# clock.net
KiCad netlist of a schematic drawn in EAGLE
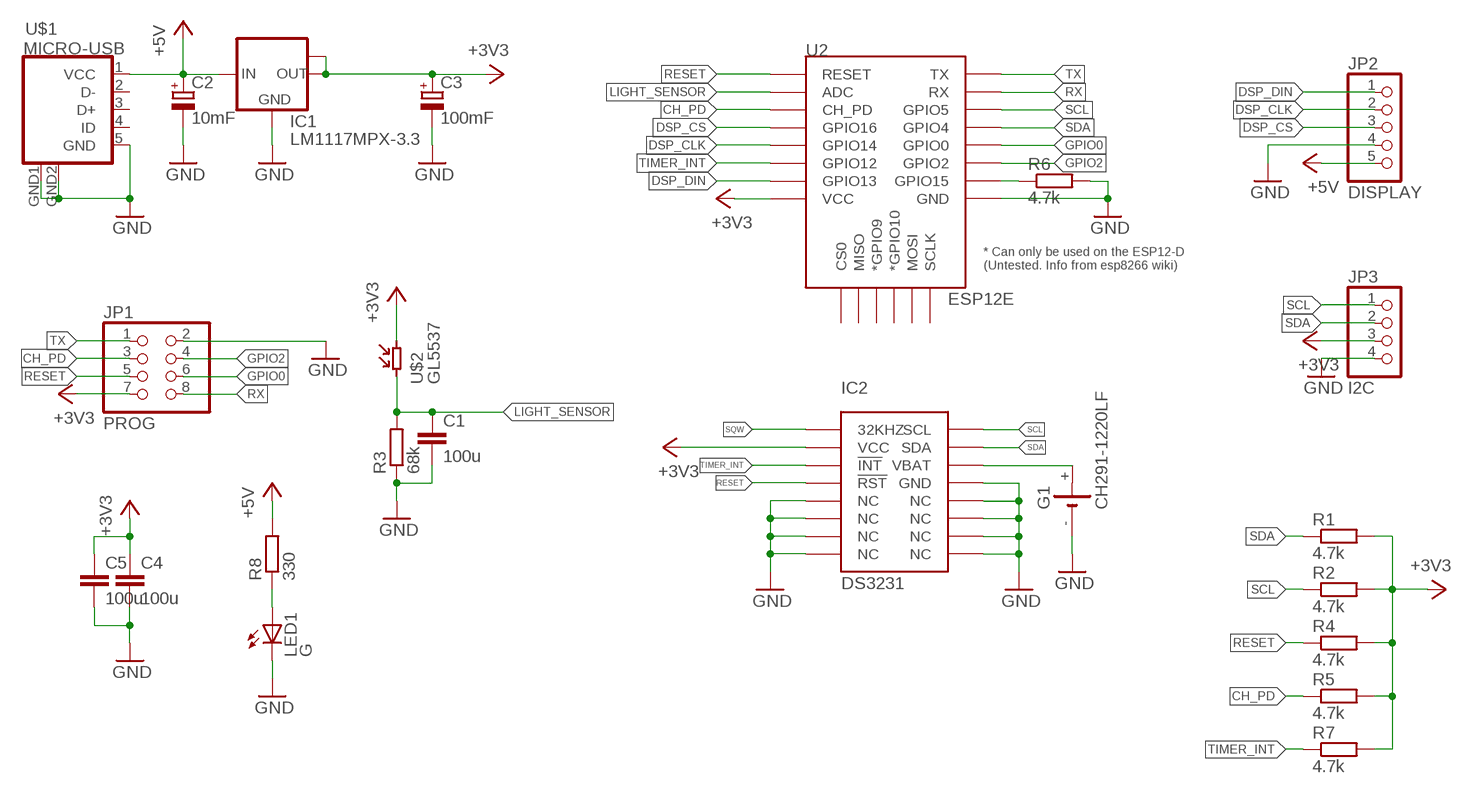
[diagram p0: schematic, sheet 1]

(export (version "E")
  (design (tool "Eeschema 10.0.6"))
  (components
    (comp (ref "C1")
      (value "100u")
      (footprint "eagle-import:C0805")
      (libsource (lib "eagle-import") (part "C-EUC0805"))
    )
    (comp (ref "C2")
      (value "10mF")
      (footprint "eagle-import:A_3216-18W")
      (libsource (lib "eagle-import") (part "CPOL-EUA/3216-18W"))
    )
    (comp (ref "C3")
      (value "100mF")
      (footprint "eagle-import:A_3216-18W")
      (libsource (lib "eagle-import") (part "CPOL-EUA/3216-18W"))
    )
    (comp (ref "C4")
      (value "100u")
      (footprint "eagle-import:C0805")
      (libsource (lib "eagle-import") (part "C-EUC0805"))
    )
    (comp (ref "C5")
      (value "100u")
      (footprint "eagle-import:C0805")
      (libsource (lib "eagle-import") (part "C-EUC0805"))
    )
    (comp (ref "G1")
      (value "CH291-1220LF")
      (footprint "eagle-import:CH291-1220LF")
      (libsource (lib "eagle-import") (part "CH291-1220LF"))
    )
    (comp (ref "IC1")
      (value "LM1117MPX-3.3")
      (footprint "eagle-import:SOT223")
      (libsource (lib "eagle-import") (part "LM1117MPX-3.3"))
    )
    (comp (ref "IC2")
      (value "DS3231")
      (footprint "eagle-import:SOIC-16W")
      (libsource (lib "eagle-import") (part "DS3231SOIC-16W"))
    )
    (comp (ref "JP1")
      (value "PROG")
      (footprint "eagle-import:2X04")
      (libsource (lib "eagle-import") (part "PINHD-2X4"))
    )
    (comp (ref "JP2")
      (value "DISPLAY")
      (footprint "eagle-import:1X05")
      (libsource (lib "eagle-import") (part "PINHD-1X5"))
    )
    (comp (ref "JP3")
      (value "I2C")
      (footprint "eagle-import:1X04")
      (libsource (lib "eagle-import") (part "PINHD-1X4"))
    )
    (comp (ref "LED1")
      (value "G")
      (footprint "eagle-import:CHIPLED_0805")
      (libsource (lib "eagle-import") (part "LEDCHIPLED_0805"))
    )
    (comp (ref "R1")
      (value "4.7k")
      (footprint "eagle-import:M0805")
      (libsource (lib "eagle-import") (part "R-EU_M0805"))
    )
    (comp (ref "R2")
      (value "4.7k")
      (footprint "eagle-import:M0805")
      (libsource (lib "eagle-import") (part "R-EU_M0805"))
    )
    (comp (ref "R3")
      (value "68k")
      (footprint "eagle-import:M0805")
      (libsource (lib "eagle-import") (part "R-EU_M0805"))
    )
    (comp (ref "R4")
      (value "4.7k")
      (footprint "eagle-import:M0805")
      (libsource (lib "eagle-import") (part "R-EU_M0805"))
    )
    (comp (ref "R5")
      (value "4.7k")
      (footprint "eagle-import:M0805")
      (libsource (lib "eagle-import") (part "R-EU_M0805"))
    )
    (comp (ref "R6")
      (value "4.7k")
      (footprint "eagle-import:M0805")
      (libsource (lib "eagle-import") (part "R-EU_M0805"))
    )
    (comp (ref "R7")
      (value "4.7k")
      (footprint "eagle-import:M0805")
      (libsource (lib "eagle-import") (part "R-EU_M0805"))
    )
    (comp (ref "R8")
      (value "330")
      (footprint "eagle-import:M0805")
      (libsource (lib "eagle-import") (part "R-EU_M0805"))
    )
    (comp (ref "U$1")
      (value "MICRO-USB")
      (footprint "eagle-import:MICRO-USB")
      (libsource (lib "eagle-import") (part "MICRO-USB"))
    )
    (comp (ref "U$2")
      (value "GL5537")
      (footprint "eagle-import:GL55")
      (libsource (lib "eagle-import") (part "GL5537"))
    )
    (comp (ref "U2")
      (value "ESP12E")
      (footprint "eagle-import:ESP12E-SMD")
      (libsource (lib "eagle-import") (part "ESP12ESMD"))
    )
  )
  (nets
    (net (code "1") (name "+3V3") (class "Default")
      (node (ref "C3") (pin "+") (pinfunction "+_+") (pintype "passive"))
      (node (ref "C4") (pin "1") (pinfunction "1_1") (pintype "passive"))
      (node (ref "C5") (pin "1") (pinfunction "1_1") (pintype "passive"))
      (node (ref "IC1") (pin "2") (pinfunction "OUT_2") (pintype "passive"))
      (node (ref "IC1") (pin "TAB") (pinfunction "OUT1_TAB") (pintype "passive"))
      (node (ref "IC2") (pin "2") (pinfunction "VCC_2") (pintype "bidirectional"))
      (node (ref "JP1") (pin "7") (pinfunction "7_7") (pintype "passive"))
      (node (ref "JP3") (pin "3") (pinfunction "3_3") (pintype "passive"))
      (node (ref "R1") (pin "2") (pinfunction "2_2") (pintype "passive"))
      (node (ref "R2") (pin "2") (pinfunction "2_2") (pintype "passive"))
      (node (ref "R4") (pin "2") (pinfunction "2_2") (pintype "passive"))
      (node (ref "R5") (pin "2") (pinfunction "2_2") (pintype "passive"))
      (node (ref "R7") (pin "2") (pinfunction "2_2") (pintype "passive"))
      (node (ref "U$2") (pin "P$2") (pinfunction "P$2_P$2") (pintype "passive"))
      (node (ref "U2") (pin "VCC") (pinfunction "VCC_VCC") (pintype "bidirectional"))
    )
    (net (code "2") (name "+5V") (class "Default")
      (node (ref "C2") (pin "+") (pinfunction "+_+") (pintype "passive"))
      (node (ref "IC1") (pin "3") (pinfunction "IN_3") (pintype "input"))
      (node (ref "JP2") (pin "5") (pinfunction "5_5") (pintype "passive"))
      (node (ref "R8") (pin "2") (pinfunction "2_2") (pintype "passive"))
      (node (ref "U$1") (pin "1") (pinfunction "VCC_1") (pintype "power_in"))
    )
    (net (code "3") (name "CH_PD") (class "Default")
      (node (ref "JP1") (pin "3") (pinfunction "3_3") (pintype "passive"))
      (node (ref "R5") (pin "1") (pinfunction "1_1") (pintype "passive"))
      (node (ref "U2") (pin "CH_PD") (pinfunction "CH_PD_CH_PD") (pintype "bidirectional"))
    )
    (net (code "4") (name "DSP_CLK") (class "Default")
      (node (ref "JP2") (pin "2") (pinfunction "2_2") (pintype "passive"))
      (node (ref "U2") (pin "GPIO14") (pinfunction "GPIO14_GPIO14") (pintype "bidirectional"))
    )
    (net (code "5") (name "DSP_CS") (class "Default")
      (node (ref "JP2") (pin "3") (pinfunction "3_3") (pintype "passive"))
      (node (ref "U2") (pin "GPIO16") (pinfunction "GPIO16_GPIO16") (pintype "bidirectional"))
    )
    (net (code "6") (name "DSP_DIN") (class "Default")
      (node (ref "JP2") (pin "1") (pinfunction "1_1") (pintype "passive"))
      (node (ref "U2") (pin "GPIO13") (pinfunction "GPIO13_GPIO13") (pintype "bidirectional"))
    )
    (net (code "7") (name "GND") (class "Default")
      (node (ref "C1") (pin "2") (pinfunction "2_2") (pintype "passive"))
      (node (ref "C2") (pin "-") (pinfunction "-_-") (pintype "passive"))
      (node (ref "C3") (pin "-") (pinfunction "-_-") (pintype "passive"))
      (node (ref "C4") (pin "2") (pinfunction "2_2") (pintype "passive"))
      (node (ref "C5") (pin "2") (pinfunction "2_2") (pintype "passive"))
      (node (ref "G1") (pin "-") (pinfunction "-_-") (pintype "passive"))
      (node (ref "IC1") (pin "1") (pinfunction "GND_1") (pintype "input"))
      (node (ref "IC2") (pin "10") (pinfunction "NC_10") (pintype "bidirectional"))
      (node (ref "IC2") (pin "11") (pinfunction "NC_11") (pintype "bidirectional"))
      (node (ref "IC2") (pin "12") (pinfunction "NC_12") (pintype "bidirectional"))
      (node (ref "IC2") (pin "13") (pinfunction "GND_13") (pintype "bidirectional"))
      (node (ref "IC2") (pin "5") (pinfunction "NC_5") (pintype "bidirectional"))
      (node (ref "IC2") (pin "6") (pinfunction "NC_6") (pintype "bidirectional"))
      (node (ref "IC2") (pin "7") (pinfunction "NC_7") (pintype "bidirectional"))
      (node (ref "IC2") (pin "8") (pinfunction "NC_8") (pintype "bidirectional"))
      (node (ref "IC2") (pin "9") (pinfunction "NC_9") (pintype "bidirectional"))
      (node (ref "JP1") (pin "2") (pinfunction "2_2") (pintype "passive"))
      (node (ref "JP2") (pin "4") (pinfunction "4_4") (pintype "passive"))
      (node (ref "JP3") (pin "4") (pinfunction "4_4") (pintype "passive"))
      (node (ref "LED1") (pin "C") (pinfunction "C_C") (pintype "passive"))
      (node (ref "R3") (pin "1") (pinfunction "1_1") (pintype "passive"))
      (node (ref "R6") (pin "2") (pinfunction "2_2") (pintype "passive"))
      (node (ref "U$1") (pin "5") (pinfunction "GND_5") (pintype "power_in"))
      (node (ref "U$1") (pin "GND1") (pinfunction "GND_GND1") (pintype "power_in"))
      (node (ref "U$1") (pin "GND2") (pinfunction "GND_GND2") (pintype "power_in"))
      (node (ref "U2") (pin "GND") (pinfunction "GND_GND") (pintype "bidirectional"))
    )
    (net (code "8") (name "GPIO0") (class "Default")
      (node (ref "JP1") (pin "6") (pinfunction "6_6") (pintype "passive"))
      (node (ref "U2") (pin "GPIO0") (pinfunction "GPIO0_GPIO0") (pintype "bidirectional"))
    )
    (net (code "9") (name "GPIO2") (class "Default")
      (node (ref "JP1") (pin "4") (pinfunction "4_4") (pintype "passive"))
      (node (ref "U2") (pin "GPIO2") (pinfunction "GPIO2_GPIO2") (pintype "bidirectional"))
    )
    (net (code "10") (name "LIGHT_SENSOR") (class "Default")
      (node (ref "C1") (pin "1") (pinfunction "1_1") (pintype "passive"))
      (node (ref "R3") (pin "2") (pinfunction "2_2") (pintype "passive"))
      (node (ref "U$2") (pin "P$1") (pinfunction "P$1_P$1") (pintype "passive"))
      (node (ref "U2") (pin "ADC") (pinfunction "ADC_ADC") (pintype "bidirectional"))
    )
    (net (code "11") (name "Net-(IC2-VBAT)") (class "Default")
      (node (ref "G1") (pin "+") (pinfunction "+_+") (pintype "passive"))
      (node (ref "IC2") (pin "14") (pinfunction "VBAT_14") (pintype "bidirectional"))
    )
    (net (code "12") (name "Net-(LED1-PadA)") (class "Default")
      (node (ref "LED1") (pin "A") (pinfunction "A_A") (pintype "passive"))
      (node (ref "R8") (pin "1") (pinfunction "1_1") (pintype "passive"))
    )
    (net (code "13") (name "Net-(R6-Pad1)") (class "Default")
      (node (ref "R6") (pin "1") (pinfunction "1_1") (pintype "passive"))
      (node (ref "U2") (pin "GPIO15") (pinfunction "GPIO15_GPIO15") (pintype "bidirectional"))
    )
    (net (code "14") (name "RESET") (class "Default")
      (node (ref "IC2") (pin "4") (pinfunction "~{RST}_4") (pintype "bidirectional"))
      (node (ref "JP1") (pin "5") (pinfunction "5_5") (pintype "passive"))
      (node (ref "R4") (pin "1") (pinfunction "1_1") (pintype "passive"))
      (node (ref "U2") (pin "RESET") (pinfunction "RESET_RESET") (pintype "bidirectional"))
    )
    (net (code "15") (name "RX") (class "Default")
      (node (ref "JP1") (pin "8") (pinfunction "8_8") (pintype "passive"))
      (node (ref "U2") (pin "RXD0") (pinfunction "RX_RXD0") (pintype "bidirectional"))
    )
    (net (code "16") (name "SCL") (class "Default")
      (node (ref "IC2") (pin "16") (pinfunction "SCL_16") (pintype "bidirectional"))
      (node (ref "JP3") (pin "1") (pinfunction "1_1") (pintype "passive"))
      (node (ref "R2") (pin "1") (pinfunction "1_1") (pintype "passive"))
      (node (ref "U2") (pin "GPIO5") (pinfunction "GPIO5_GPIO5") (pintype "bidirectional"))
    )
    (net (code "17") (name "SDA") (class "Default")
      (node (ref "IC2") (pin "15") (pinfunction "SDA_15") (pintype "bidirectional"))
      (node (ref "JP3") (pin "2") (pinfunction "2_2") (pintype "passive"))
      (node (ref "R1") (pin "1") (pinfunction "1_1") (pintype "passive"))
      (node (ref "U2") (pin "GPIO4") (pinfunction "GPIO4_GPIO4") (pintype "bidirectional"))
    )
    (net (code "18") (name "SQW") (class "Default")
      (node (ref "IC2") (pin "1") (pinfunction "32KHZ_1") (pintype "bidirectional"))
    )
    (net (code "19") (name "TIMER_INT") (class "Default")
      (node (ref "IC2") (pin "3") (pinfunction "~{INT}_3") (pintype "bidirectional"))
      (node (ref "R7") (pin "1") (pinfunction "1_1") (pintype "passive"))
      (node (ref "U2") (pin "GPIO12") (pinfunction "GPIO12_GPIO12") (pintype "bidirectional"))
    )
    (net (code "20") (name "TX") (class "Default")
      (node (ref "JP1") (pin "1") (pinfunction "1_1") (pintype "passive"))
      (node (ref "U2") (pin "TXD0") (pinfunction "TX_TXD0") (pintype "bidirectional"))
    )
    (net (code "21") (name "unconnected-(U$1-D+-Pad3)") (class "Default")
      (node (ref "U$1") (pin "3") (pinfunction "D+_3") (pintype "bidirectional"))
    )
    (net (code "22") (name "unconnected-(U$1-D--Pad2)") (class "Default")
      (node (ref "U$1") (pin "2") (pinfunction "D-_2") (pintype "bidirectional"))
    )
    (net (code "23") (name "unconnected-(U$1-ID-Pad4)") (class "Default")
      (node (ref "U$1") (pin "4") (pinfunction "ID_4") (pintype "bidirectional"))
    )
    (net (code "24") (name "unconnected-(U2-*GPIO9-PadGPIO9)") (class "Default")
      (node (ref "U2") (pin "GPIO9") (pinfunction "*GPIO9_GPIO9") (pintype "bidirectional"))
    )
    (net (code "25") (name "unconnected-(U2-*GPIO10-PadGPIO10)") (class "Default")
      (node (ref "U2") (pin "GPIO10") (pinfunction "*GPIO10_GPIO10") (pintype "bidirectional"))
    )
    (net (code "26") (name "unconnected-(U2-PadCS0)") (class "Default")
      (node (ref "U2") (pin "CS0") (pinfunction "CS0_CS0") (pintype "bidirectional"))
    )
    (net (code "27") (name "unconnected-(U2-PadMISO)") (class "Default")
      (node (ref "U2") (pin "MISO") (pinfunction "MISO_MISO") (pintype "bidirectional"))
    )
    (net (code "28") (name "unconnected-(U2-PadMOSI)") (class "Default")
      (node (ref "U2") (pin "MOSI") (pinfunction "MOSI_MOSI") (pintype "bidirectional"))
    )
    (net (code "29") (name "unconnected-(U2-PadSCLK)") (class "Default")
      (node (ref "U2") (pin "SCLK") (pinfunction "SCLK_SCLK") (pintype "bidirectional"))
    )
  )
)
